# 2-RJ45.net
KiCad netlist of a schematic drawn in Altium Designer
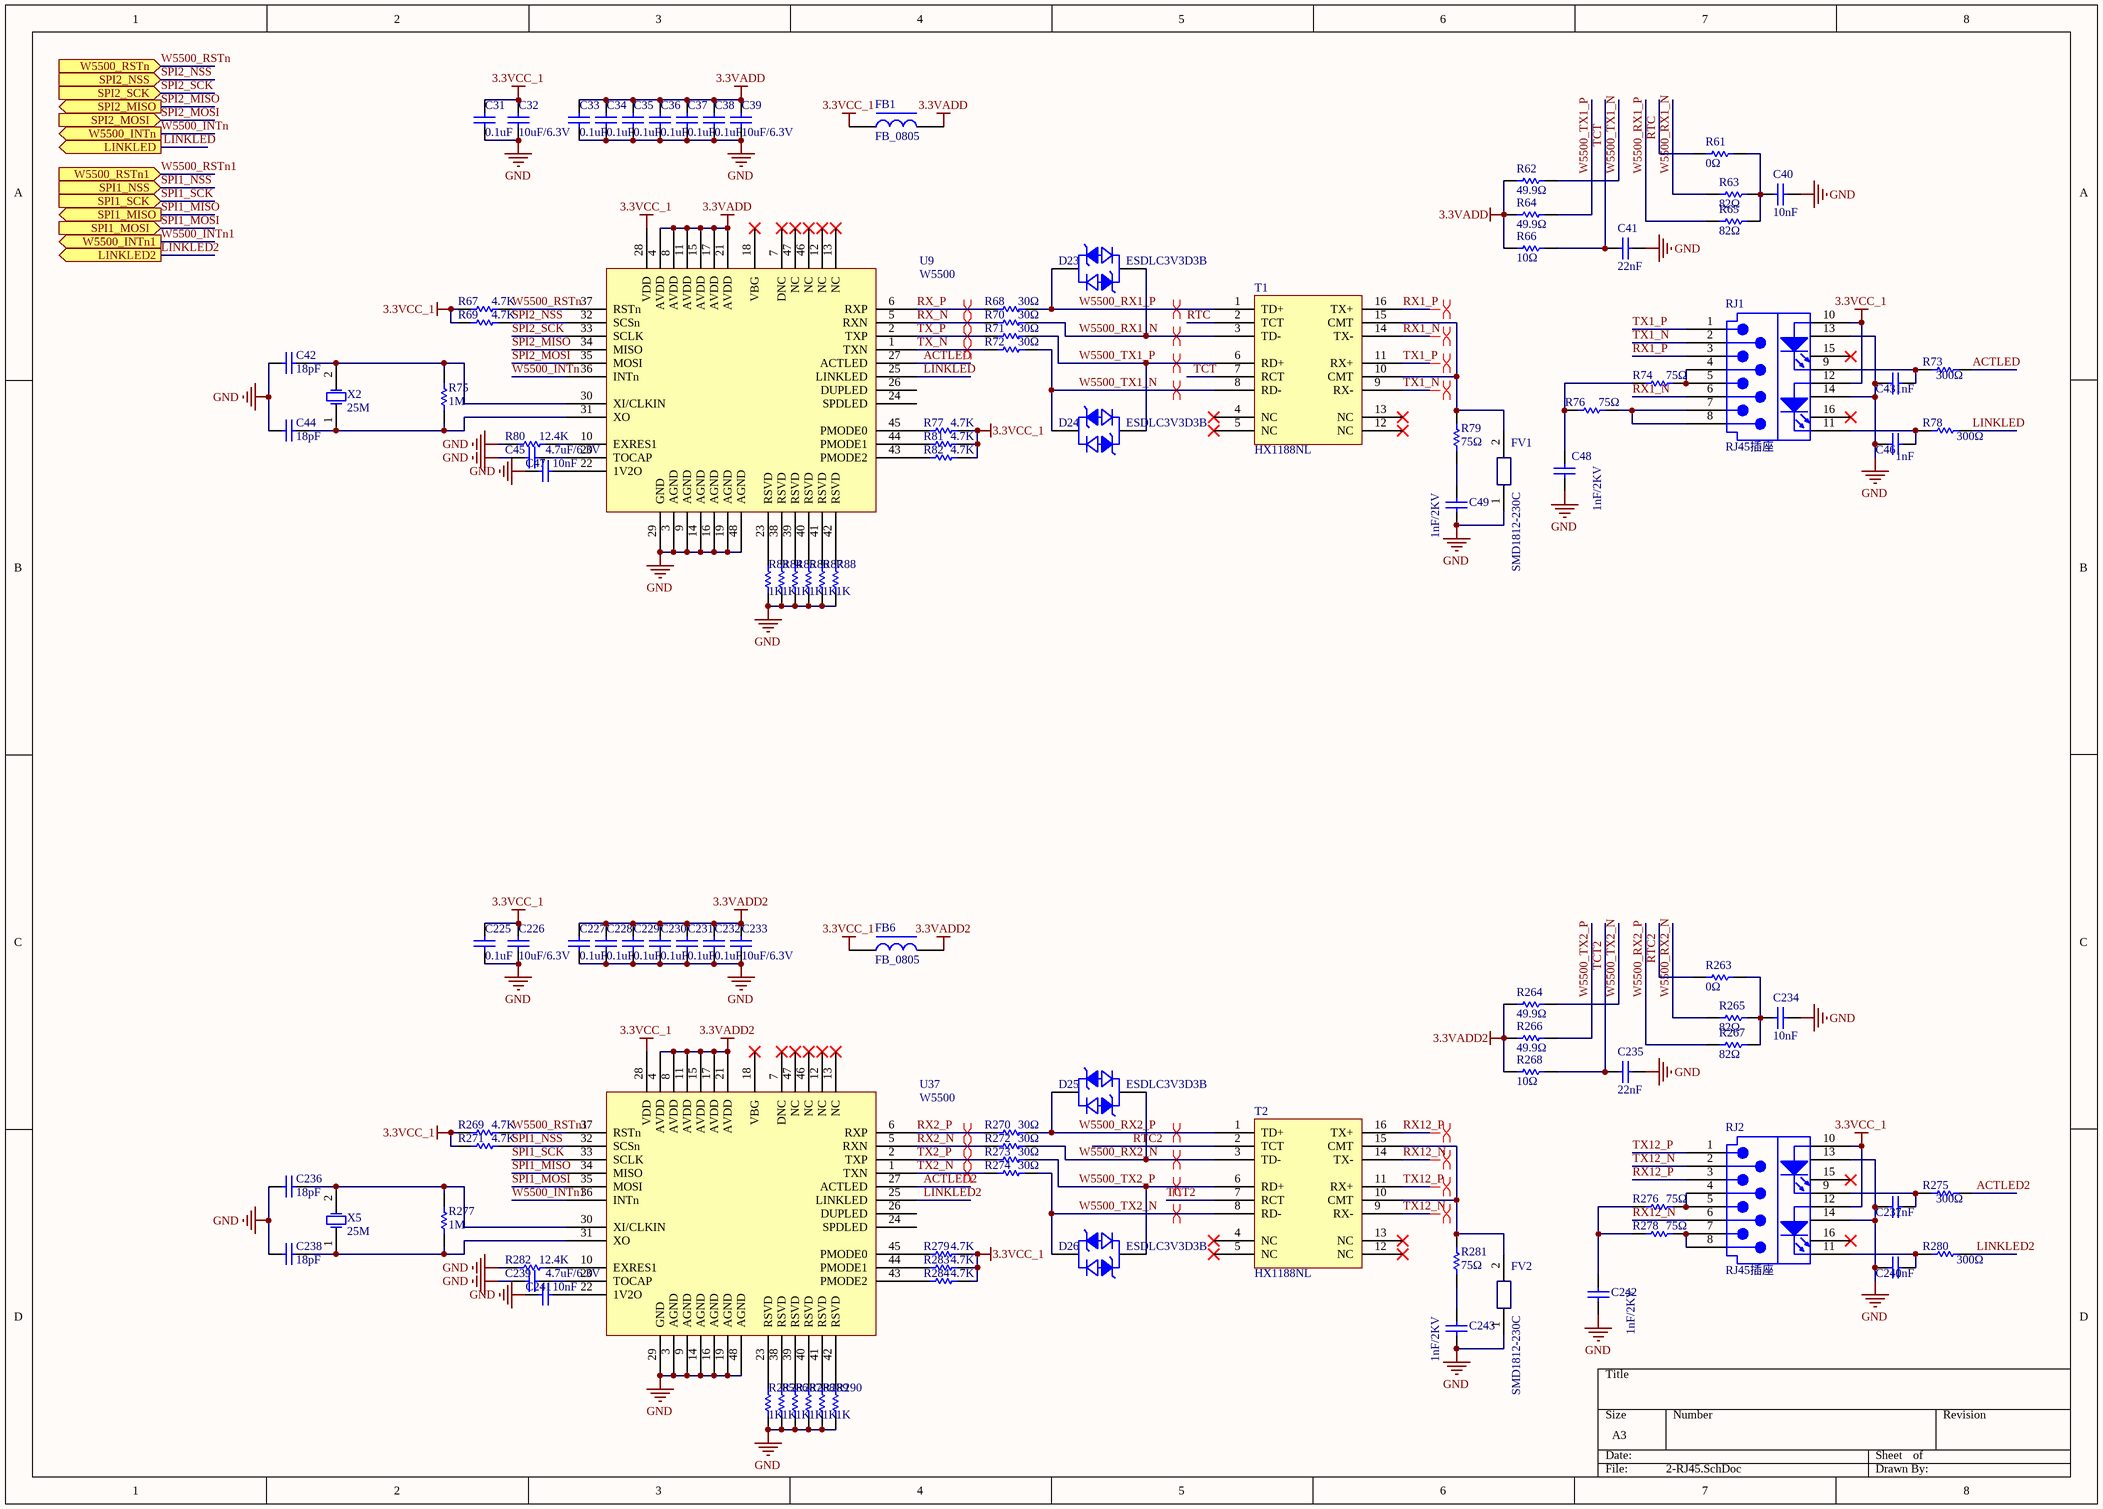
[diagram p0: 2-RJ45.SchDoc]

(export (version "E")
  (design (tool "Eeschema 10.0.6"))
  (components
    (comp (ref "C31")
      (value "0.1uF")
      (footprint "C0603")
      (description "贴片电容_GRM188R71H104KA01D_0.1uF±10%,50V,0603")
      (libsource (lib "20贴片电容0603") (part "0.1uF贴片电容"))
    )
    (comp (ref "C32")
      (value "10uF/6.3V")
      (footprint "C0603")
      (description "贴片电容_GRM188R60J106ME47D_10uF±20%,6.3V,0603")
      (libsource (lib "20贴片电容0603") (part "10uF贴片电容"))
    )
    (comp (ref "C33")
      (value "0.1uF")
      (footprint "C0603")
      (description "贴片电容_GRM188R71H104KA01D_0.1uF±10%,50V,0603")
      (libsource (lib "20贴片电容0603") (part "0.1uF贴片电容"))
    )
    (comp (ref "C34")
      (value "0.1uF")
      (footprint "C0603")
      (description "贴片电容_GRM188R71H104KA01D_0.1uF±10%,50V,0603")
      (libsource (lib "20贴片电容0603") (part "0.1uF贴片电容"))
    )
    (comp (ref "C35")
      (value "0.1uF")
      (footprint "C0603")
      (description "贴片电容_GRM188R71H104KA01D_0.1uF±10%,50V,0603")
      (libsource (lib "20贴片电容0603") (part "0.1uF贴片电容"))
    )
    (comp (ref "C36")
      (value "0.1uF")
      (footprint "C0603")
      (description "贴片电容_GRM188R71H104KA01D_0.1uF±10%,50V,0603")
      (libsource (lib "20贴片电容0603") (part "0.1uF贴片电容"))
    )
    (comp (ref "C37")
      (value "0.1uF")
      (footprint "C0603")
      (description "贴片电容_GRM188R71H104KA01D_0.1uF±10%,50V,0603")
      (libsource (lib "20贴片电容0603") (part "0.1uF贴片电容"))
    )
    (comp (ref "C38")
      (value "0.1uF")
      (footprint "C0603")
      (description "贴片电容_GRM188R71H104KA01D_0.1uF±10%,50V,0603")
      (libsource (lib "20贴片电容0603") (part "0.1uF贴片电容"))
    )
    (comp (ref "C39")
      (value "10uF/6.3V")
      (footprint "C0603")
      (description "贴片电容_GRM188R60J106ME47D_10uF±20%,6.3V,0603")
      (libsource (lib "20贴片电容0603") (part "10uF贴片电容"))
    )
    (comp (ref "C40")
      (value "10nF")
      (footprint "C0603")
      (description "C0603C103K5RAC_10nF±10%,50V,0603")
      (fields (field (name "MPN") "KEMET"))
      (libsource (lib "20贴片电容0603") (part "0.1uF贴片电容"))
    )
    (comp (ref "C41")
      (value "22nF")
      (footprint "C0603")
      (description "贴片电容_22nF±5%,50V,0603")
      (libsource (lib "20贴片电容0603") (part "27nF贴片电容"))
    )
    (comp (ref "C42")
      (value "18pF")
      (footprint "C0603")
      (description "贴片电容_GRM1885C1H180JA01D_18pF±5%,50V,0603")
      (libsource (lib "20贴片电容0603") (part "18pF贴片电容"))
    )
    (comp (ref "C43")
      (value "1nF")
      (footprint "C0603")
      (description "贴片电容_GRM188R71H102KA01_1000pF±10%,50V,0603")
      (libsource (lib "20贴片电容0603") (part "1000pF贴片电容"))
    )
    (comp (ref "C44")
      (value "18pF")
      (footprint "C0603")
      (description "贴片电容_GRM1885C1H180JA01D_18pF±5%,50V,0603")
      (libsource (lib "20贴片电容0603") (part "18pF贴片电容"))
    )
    (comp (ref "C45")
      (value "4.7uF/6.3V")
      (footprint "C0603")
      (description "GRM188R61C475K_4.7uF±10%,16V,0603")
      (fields (field (name "MPN") "Murata"))
      (libsource (lib "20贴片电容0603") (part "1uF贴片电容"))
    )
    (comp (ref "C46")
      (value "1nF")
      (footprint "C0603")
      (description "贴片电容_GRM188R71H102KA01_1000pF±10%,50V,0603")
      (libsource (lib "20贴片电容0603") (part "1000pF贴片电容"))
    )
    (comp (ref "C47")
      (value "10nF")
      (footprint "C0603")
      (description "C0603C103K5RAC_10nF±10%,50V,0603")
      (fields (field (name "MPN") "KEMET"))
      (libsource (lib "20贴片电容0603") (part "0.1uF贴片电容"))
    )
    (comp (ref "C48")
      (value "1nF/2KV")
      (footprint "C1206")
      (description "贴片电容_1206B102K202NT_1206,1000PF/2KV")
      (fields (field (name "MPN") "风华"))
      (libsource (lib "22贴片电容1210") (part "10uF贴片电容"))
    )
    (comp (ref "C49")
      (value "1nF/2KV")
      (footprint "C1206")
      (description "贴片电容_1206B102K202NT_1206,1000PF/2KV")
      (fields (field (name "MPN") "风华"))
      (libsource (lib "22贴片电容1210") (part "10uF贴片电容"))
    )
    (comp (ref "C225")
      (value "0.1uF")
      (footprint "C0603")
      (description "贴片电容_GRM188R71H104KA01D_0.1uF±10%,50V,0603")
      (libsource (lib "20贴片电容0603") (part "0.1uF贴片电容"))
    )
    (comp (ref "C226")
      (value "10uF/6.3V")
      (footprint "C0603")
      (description "贴片电容_GRM188R60J106ME47D_10uF±20%,6.3V,0603")
      (libsource (lib "20贴片电容0603") (part "10uF贴片电容"))
    )
    (comp (ref "C227")
      (value "0.1uF")
      (footprint "C0603")
      (description "贴片电容_GRM188R71H104KA01D_0.1uF±10%,50V,0603")
      (libsource (lib "20贴片电容0603") (part "0.1uF贴片电容"))
    )
    (comp (ref "C228")
      (value "0.1uF")
      (footprint "C0603")
      (description "贴片电容_GRM188R71H104KA01D_0.1uF±10%,50V,0603")
      (libsource (lib "20贴片电容0603") (part "0.1uF贴片电容"))
    )
    (comp (ref "C229")
      (value "0.1uF")
      (footprint "C0603")
      (description "贴片电容_GRM188R71H104KA01D_0.1uF±10%,50V,0603")
      (libsource (lib "20贴片电容0603") (part "0.1uF贴片电容"))
    )
    (comp (ref "C230")
      (value "0.1uF")
      (footprint "C0603")
      (description "贴片电容_GRM188R71H104KA01D_0.1uF±10%,50V,0603")
      (libsource (lib "20贴片电容0603") (part "0.1uF贴片电容"))
    )
    (comp (ref "C231")
      (value "0.1uF")
      (footprint "C0603")
      (description "贴片电容_GRM188R71H104KA01D_0.1uF±10%,50V,0603")
      (libsource (lib "20贴片电容0603") (part "0.1uF贴片电容"))
    )
    (comp (ref "C232")
      (value "0.1uF")
      (footprint "C0603")
      (description "贴片电容_GRM188R71H104KA01D_0.1uF±10%,50V,0603")
      (libsource (lib "20贴片电容0603") (part "0.1uF贴片电容"))
    )
    (comp (ref "C233")
      (value "10uF/6.3V")
      (footprint "C0603")
      (description "贴片电容_GRM188R60J106ME47D_10uF±20%,6.3V,0603")
      (libsource (lib "20贴片电容0603") (part "10uF贴片电容"))
    )
    (comp (ref "C234")
      (value "10nF")
      (footprint "C0603")
      (description "C0603C103K5RAC_10nF±10%,50V,0603")
      (fields (field (name "MPN") "KEMET"))
      (libsource (lib "20贴片电容0603") (part "0.1uF贴片电容"))
    )
    (comp (ref "C235")
      (value "22nF")
      (footprint "C0603")
      (description "贴片电容_22nF±5%,50V,0603")
      (libsource (lib "20贴片电容0603") (part "27nF贴片电容"))
    )
    (comp (ref "C236")
      (value "18pF")
      (footprint "C0603")
      (description "贴片电容_GRM1885C1H180JA01D_18pF±5%,50V,0603")
      (libsource (lib "20贴片电容0603") (part "18pF贴片电容"))
    )
    (comp (ref "C237")
      (value "1nF")
      (footprint "C0603")
      (description "贴片电容_GRM188R71H102KA01_1000pF±10%,50V,0603")
      (libsource (lib "20贴片电容0603") (part "1000pF贴片电容"))
    )
    (comp (ref "C238")
      (value "18pF")
      (footprint "C0603")
      (description "贴片电容_GRM1885C1H180JA01D_18pF±5%,50V,0603")
      (libsource (lib "20贴片电容0603") (part "18pF贴片电容"))
    )
    (comp (ref "C239")
      (value "4.7uF/6.3V")
      (footprint "C0603")
      (description "GRM188R61C475K_4.7uF±10%,16V,0603")
      (fields (field (name "MPN") "Murata"))
      (libsource (lib "20贴片电容0603") (part "1uF贴片电容"))
    )
    (comp (ref "C240")
      (value "1nF")
      (footprint "C0603")
      (description "贴片电容_GRM188R71H102KA01_1000pF±10%,50V,0603")
      (libsource (lib "20贴片电容0603") (part "1000pF贴片电容"))
    )
    (comp (ref "C241")
      (value "10nF")
      (footprint "C0603")
      (description "C0603C103K5RAC_10nF±10%,50V,0603")
      (fields (field (name "MPN") "KEMET"))
      (libsource (lib "20贴片电容0603") (part "0.1uF贴片电容"))
    )
    (comp (ref "C242")
      (value "1nF/2KV")
      (footprint "C1206")
      (description "贴片电容_1000pF/2KV")
      (libsource (lib "22贴片电容1210") (part "10uF贴片电容"))
    )
    (comp (ref "C243")
      (value "1nF/2KV")
      (footprint "C1206")
      (description "贴片电容_1000pF/2KV")
      (libsource (lib "22贴片电容1210") (part "10uF贴片电容"))
    )
    (comp (ref "D23")
      (value "ESDLC3V3D3B")
      (footprint "SOD-323")
      (description "ESD_ESDLC3V3D3B _SOD-323封装")
      (libsource (lib "40二极管") (part "ESDLC3V3D3B"))
    )
    (comp (ref "D24")
      (value "ESDLC3V3D3B")
      (footprint "SOD-323")
      (description "ESD_ESDLC3V3D3B _SOD-323封装")
      (libsource (lib "40二极管") (part "ESDLC3V3D3B"))
    )
    (comp (ref "D25")
      (value "ESDLC3V3D3B")
      (footprint "SOD-323")
      (description "ESD_ESDLC3V3D3B _SOD-323封装")
      (libsource (lib "40二极管") (part "ESDLC3V3D3B"))
    )
    (comp (ref "D26")
      (value "ESDLC3V3D3B")
      (footprint "SOD-323")
      (description "ESD_ESDLC3V3D3B _SOD-323封装")
      (libsource (lib "40二极管") (part "ESDLC3V3D3B"))
    )
    (comp (ref "FB1")
      (value "FB_0805")
      (footprint "L0805")
      (description "贴片磁珠_600R,0805")
      (libsource (lib "32贴片磁珠0805") (part "0805贴片磁珠"))
    )
    (comp (ref "FB6")
      (value "FB_0805")
      (footprint "L0805")
      (description "贴片磁珠_600R,0805")
      (libsource (lib "32贴片磁珠0805") (part "0805贴片磁珠"))
    )
    (comp (ref "FV1")
      (value "SMD1812-230C")
      (footprint "D1812")
      (description "贴片陶瓷气体放电管_SMD1812-230C_1812,230V,2KA")
      (fields (field (name "MPN") "Littelfuse"))
      (libsource (lib "104气体放电管") (part "4532-401-LF"))
    )
    (comp (ref "FV2")
      (value "SMD1812-230C")
      (footprint "D1812")
      (description "贴片陶瓷气体放电管_SMD1812-230C_1812,230V,2KA")
      (fields (field (name "MPN") "Littelfuse"))
      (libsource (lib "104气体放电管") (part "4532-401-LF"))
    )
    (comp (ref "R61")
      (value "0Ω")
      (footprint "R0603")
      (description "贴片电阻_0Ω±5%,0603")
      (libsource (lib "10贴片电阻0603") (part "0Ω贴片电阻"))
    )
    (comp (ref "R62")
      (value "49.9Ω")
      (footprint "R0603")
      (description "贴片电阻_49.9Ω±1%,0603")
      (libsource (lib "10贴片电阻0603") (part "51Ω贴片电阻"))
    )
    (comp (ref "R63")
      (value "82Ω")
      (footprint "R0603")
      (description "贴片电阻_82Ω±1%,0603")
      (libsource (lib "10贴片电阻0603") (part "51Ω贴片电阻"))
    )
    (comp (ref "R64")
      (value "49.9Ω")
      (footprint "R0603")
      (description "贴片电阻_49.9Ω±1%,0603")
      (libsource (lib "10贴片电阻0603") (part "51Ω贴片电阻"))
    )
    (comp (ref "R65")
      (value "82Ω")
      (footprint "R0603")
      (description "贴片电阻_82Ω±1%,0603")
      (libsource (lib "10贴片电阻0603") (part "51Ω贴片电阻"))
    )
    (comp (ref "R66")
      (value "10Ω")
      (footprint "R0603")
      (description "贴片电阻_10Ω±5%,0603")
      (libsource (lib "10贴片电阻0603") (part "10Ω贴片电阻"))
    )
    (comp (ref "R67")
      (value "4.7K")
      (footprint "R0603")
      (description "贴片电阻_4.7K±5%,0603")
      (libsource (lib "10贴片电阻0603") (part "4.7K贴片电阻"))
    )
    (comp (ref "R68")
      (value "30Ω")
      (footprint "R0603")
      (description "贴片电阻_30Ω±5%,0603")
      (libsource (lib "10贴片电阻0603") (part "30Ω贴片电阻"))
    )
    (comp (ref "R69")
      (value "4.7K")
      (footprint "R0603")
      (description "贴片电阻_4.7K±5%,0603")
      (libsource (lib "10贴片电阻0603") (part "4.7K贴片电阻"))
    )
    (comp (ref "R70")
      (value "30Ω")
      (footprint "R0603")
      (description "贴片电阻_30Ω±5%,0603")
      (libsource (lib "10贴片电阻0603") (part "30Ω贴片电阻"))
    )
    (comp (ref "R71")
      (value "30Ω")
      (footprint "R0603")
      (description "贴片电阻_30Ω±5%,0603")
      (libsource (lib "10贴片电阻0603") (part "30Ω贴片电阻"))
    )
    (comp (ref "R72")
      (value "30Ω")
      (footprint "R0603")
      (description "贴片电阻_30Ω±5%,0603")
      (libsource (lib "10贴片电阻0603") (part "30Ω贴片电阻"))
    )
    (comp (ref "R73")
      (value "300Ω")
      (footprint "R0603")
      (description "贴片电阻_300Ω±5%,0603")
      (libsource (lib "10贴片电阻0603") (part "300Ω贴片电阻"))
    )
    (comp (ref "R74")
      (value "75Ω")
      (footprint "R0805")
      (description "贴片电阻_75Ω±5%,0805")
      (libsource (lib "11贴片电阻0805") (part "75Ω贴片电阻"))
    )
    (comp (ref "R75")
      (value "1M")
      (footprint "R0603")
      (description "贴片电阻_1M±5%,0603")
      (libsource (lib "10贴片电阻0603") (part "1M贴片电阻"))
    )
    (comp (ref "R76")
      (value "75Ω")
      (footprint "R0805")
      (description "贴片电阻_75Ω±5%,0805")
      (libsource (lib "11贴片电阻0805") (part "75Ω贴片电阻"))
    )
    (comp (ref "R77")
      (value "4.7K")
      (footprint "R0603")
      (description "贴片电阻_4.7K±5%,0603")
      (libsource (lib "10贴片电阻0603") (part "4.7K贴片电阻"))
    )
    (comp (ref "R78")
      (value "300Ω")
      (footprint "R0603")
      (description "贴片电阻_300Ω±5%,0603")
      (libsource (lib "10贴片电阻0603") (part "300Ω贴片电阻"))
    )
    (comp (ref "R79")
      (value "75Ω")
      (footprint "R1206")
      (description "贴片电阻_75Ω±5%,1206")
      (libsource (lib "11贴片电阻0805") (part "75Ω贴片电阻"))
    )
    (comp (ref "R80")
      (value "12.4K")
      (footprint "R0603")
      (description "贴片电阻_12.4K±1%,0603")
      (libsource (lib "10贴片电阻0603") (part "12K贴片电阻"))
    )
    (comp (ref "R81")
      (value "4.7K")
      (footprint "R0603")
      (description "贴片电阻_4.7K±5%,0603")
      (libsource (lib "10贴片电阻0603") (part "4.7K贴片电阻"))
    )
    (comp (ref "R82")
      (value "4.7K")
      (footprint "R0603")
      (description "贴片电阻_4.7K±5%,0603")
      (libsource (lib "10贴片电阻0603") (part "4.7K贴片电阻"))
    )
    (comp (ref "R83")
      (value "1K")
      (footprint "R0603")
      (description "贴片电阻_1K±5%,0603")
      (libsource (lib "10贴片电阻0603") (part "1K贴片电阻"))
    )
    (comp (ref "R84")
      (value "1K")
      (footprint "R0603")
      (description "贴片电阻_1K±5%,0603")
      (libsource (lib "10贴片电阻0603") (part "1K贴片电阻"))
    )
    (comp (ref "R85")
      (value "1K")
      (footprint "R0603")
      (description "贴片电阻_1K±5%,0603")
      (libsource (lib "10贴片电阻0603") (part "1K贴片电阻"))
    )
    (comp (ref "R86")
      (value "1K")
      (footprint "R0603")
      (description "贴片电阻_1K±5%,0603")
      (libsource (lib "10贴片电阻0603") (part "1K贴片电阻"))
    )
    (comp (ref "R87")
      (value "1K")
      (footprint "R0603")
      (description "贴片电阻_1K±5%,0603")
      (libsource (lib "10贴片电阻0603") (part "1K贴片电阻"))
    )
    (comp (ref "R88")
      (value "1K")
      (footprint "R0603")
      (description "贴片电阻_1K±5%,0603")
      (libsource (lib "10贴片电阻0603") (part "1K贴片电阻"))
    )
    (comp (ref "R263")
      (value "0Ω")
      (footprint "R0603")
      (description "贴片电阻_0Ω±5%,0603")
      (libsource (lib "10贴片电阻0603") (part "0Ω贴片电阻"))
    )
    (comp (ref "R264")
      (value "49.9Ω")
      (footprint "R0603")
      (description "贴片电阻_49.9Ω±1%,0603")
      (libsource (lib "10贴片电阻0603") (part "51Ω贴片电阻"))
    )
    (comp (ref "R265")
      (value "82Ω")
      (footprint "R0603")
      (description "贴片电阻_82Ω±1%,0603")
      (libsource (lib "10贴片电阻0603") (part "51Ω贴片电阻"))
    )
    (comp (ref "R266")
      (value "49.9Ω")
      (footprint "R0603")
      (description "贴片电阻_49.9Ω±1%,0603")
      (libsource (lib "10贴片电阻0603") (part "51Ω贴片电阻"))
    )
    (comp (ref "R267")
      (value "82Ω")
      (footprint "R0603")
      (description "贴片电阻_82Ω±1%,0603")
      (libsource (lib "10贴片电阻0603") (part "51Ω贴片电阻"))
    )
    (comp (ref "R268")
      (value "10Ω")
      (footprint "R0603")
      (description "贴片电阻_10Ω±5%,0603")
      (libsource (lib "10贴片电阻0603") (part "10Ω贴片电阻"))
    )
    (comp (ref "R269")
      (value "4.7K")
      (footprint "R0603")
      (description "贴片电阻_4.7K±5%,0603")
      (libsource (lib "10贴片电阻0603") (part "4.7K贴片电阻"))
    )
    (comp (ref "R270")
      (value "30Ω")
      (footprint "R0603")
      (description "贴片电阻_30Ω±5%,0603")
      (libsource (lib "10贴片电阻0603") (part "30Ω贴片电阻"))
    )
    (comp (ref "R271")
      (value "4.7K")
      (footprint "R0603")
      (description "贴片电阻_4.7K±5%,0603")
      (libsource (lib "10贴片电阻0603") (part "4.7K贴片电阻"))
    )
    (comp (ref "R272")
      (value "30Ω")
      (footprint "R0603")
      (description "贴片电阻_30Ω±5%,0603")
      (libsource (lib "10贴片电阻0603") (part "30Ω贴片电阻"))
    )
    (comp (ref "R273")
      (value "30Ω")
      (footprint "R0603")
      (description "贴片电阻_30Ω±5%,0603")
      (libsource (lib "10贴片电阻0603") (part "30Ω贴片电阻"))
    )
    (comp (ref "R274")
      (value "30Ω")
      (footprint "R0603")
      (description "贴片电阻_30Ω±5%,0603")
      (libsource (lib "10贴片电阻0603") (part "30Ω贴片电阻"))
    )
    (comp (ref "R275")
      (value "300Ω")
      (footprint "R0603")
      (description "贴片电阻_300Ω±5%,0603")
      (libsource (lib "10贴片电阻0603") (part "300Ω贴片电阻"))
    )
    (comp (ref "R276")
      (value "75Ω")
      (footprint "R0805")
      (description "贴片电阻_75Ω±5%,0805")
      (libsource (lib "11贴片电阻0805") (part "75Ω贴片电阻"))
    )
    (comp (ref "R277")
      (value "1M")
      (footprint "R0603")
      (description "贴片电阻_1M±5%,0603")
      (libsource (lib "10贴片电阻0603") (part "1M贴片电阻"))
    )
    (comp (ref "R278")
      (value "75Ω")
      (footprint "R0805")
      (description "贴片电阻_75Ω±5%,0805")
      (libsource (lib "11贴片电阻0805") (part "75Ω贴片电阻"))
    )
    (comp (ref "R279")
      (value "4.7K")
      (footprint "R0603")
      (description "贴片电阻_4.7K±5%,0603")
      (libsource (lib "10贴片电阻0603") (part "4.7K贴片电阻"))
    )
    (comp (ref "R280")
      (value "300Ω")
      (footprint "R0603")
      (description "贴片电阻_300Ω±5%,0603")
      (libsource (lib "10贴片电阻0603") (part "300Ω贴片电阻"))
    )
    (comp (ref "R281")
      (value "75Ω")
      (footprint "R1206")
      (description "贴片电阻_75Ω±5%,1206")
      (libsource (lib "11贴片电阻0805") (part "75Ω贴片电阻"))
    )
    (comp (ref "R282")
      (value "12.4K")
      (footprint "R0603")
      (description "贴片电阻_12.4K±1%,0603")
      (libsource (lib "10贴片电阻0603") (part "12K贴片电阻"))
    )
    (comp (ref "R283")
      (value "4.7K")
      (footprint "R0603")
      (description "贴片电阻_4.7K±5%,0603")
      (libsource (lib "10贴片电阻0603") (part "4.7K贴片电阻"))
    )
    (comp (ref "R284")
      (value "4.7K")
      (footprint "R0603")
      (description "贴片电阻_4.7K±5%,0603")
      (libsource (lib "10贴片电阻0603") (part "4.7K贴片电阻"))
    )
    (comp (ref "R285")
      (value "1K")
      (footprint "R0603")
      (description "贴片电阻_1K±5%,0603")
      (libsource (lib "10贴片电阻0603") (part "1K贴片电阻"))
    )
    (comp (ref "R286")
      (value "1K")
      (footprint "R0603")
      (description "贴片电阻_1K±5%,0603")
      (libsource (lib "10贴片电阻0603") (part "1K贴片电阻"))
    )
    (comp (ref "R287")
      (value "1K")
      (footprint "R0603")
      (description "贴片电阻_1K±5%,0603")
      (libsource (lib "10贴片电阻0603") (part "1K贴片电阻"))
    )
    (comp (ref "R288")
      (value "1K")
      (footprint "R0603")
      (description "贴片电阻_1K±5%,0603")
      (libsource (lib "10贴片电阻0603") (part "1K贴片电阻"))
    )
    (comp (ref "R289")
      (value "1K")
      (footprint "R0603")
      (description "贴片电阻_1K±5%,0603")
      (libsource (lib "10贴片电阻0603") (part "1K贴片电阻"))
    )
    (comp (ref "R290")
      (value "1K")
      (footprint "R0603")
      (description "贴片电阻_1K±5%,0603")
      (libsource (lib "10贴片电阻0603") (part "1K贴片电阻"))
    )
    (comp (ref "RJ1")
      (value "RJ45插座")
      (footprint "RJ45TH-1x1-2R54-LED")
      (description "RJ45插座_1*1,带左黄右绿灯,弯脚")
      (fields (field (name "MPN") "朱迅"))
      (libsource (lib "91连接器") (part "RJ45弯脚带灯"))
    )
    (comp (ref "RJ2")
      (value "RJ45插座")
      (footprint "RJ45TH-1x1-2R54-LED")
      (description "RJ45插座_1*1,带左黄右绿灯,弯脚")
      (fields (field (name "MPN") "朱迅"))
      (libsource (lib "91连接器") (part "RJ45弯脚带灯"))
    )
    (comp (ref "T1")
      (value "HX1188NL")
      (footprint "SOP16-1R27-7R11x12R7")
      (description "网络变压器_HX1188NL_百兆,SOIC16")
      (libsource (lib "89网络变压器") (part "HX1188NL"))
    )
    (comp (ref "T2")
      (value "HX1188NL")
      (footprint "SOP16-1R27-7R11x12R7")
      (description "网络变压器_HX1188NL_百兆,SOIC16")
      (libsource (lib "89网络变压器") (part "HX1188NL"))
    )
    (comp (ref "U9")
      (value "W5500")
      (footprint "TQFN48-0R5-7X7")
      (description "以太网控制器_W5500_LQFP48")
      (libsource (lib "86网口芯片") (part "W5500"))
    )
    (comp (ref "U37")
      (value "W5500")
      (footprint "TQFN48-0R5-7X7")
      (description "以太网控制器_W5500_LQFP48")
      (libsource (lib "86网口芯片") (part "W5500"))
    )
    (comp (ref "X2")
      (value "25M")
      (footprint "CRY2SM-6R0x3R5")
      (description "贴片无源晶体_25MHz,30ppm,6035封装")
      (libsource (lib "60振荡器") (part "25M贴片无源晶体"))
    )
    (comp (ref "X5")
      (value "25M")
      (footprint "CRY2SM-6R0x3R5")
      (description "贴片无源晶体_25MHz,封装6035")
      (libsource (lib "60振荡器") (part "8M贴片无源晶体"))
    )
  )
  (nets
    (net (code "1") (name "/ACTLED") (class "Default")
      (node (ref "R73") (pin "2") (pinfunction "2_2") (pintype "passive"))
      (node (ref "U9") (pin "27") (pinfunction "ACTLED_27") (pintype "passive"))
    )
    (net (code "2") (name "/ACTLED2") (class "Default")
      (node (ref "R275") (pin "2") (pinfunction "2_2") (pintype "passive"))
      (node (ref "U37") (pin "27") (pinfunction "ACTLED_27") (pintype "passive"))
    )
    (net (code "3") (name "/LINKLED") (class "Default")
      (node (ref "R78") (pin "2") (pinfunction "2_2") (pintype "passive"))
      (node (ref "U9") (pin "25") (pinfunction "LINKLED_25") (pintype "passive"))
    )
    (net (code "4") (name "/LINKLED2") (class "Default")
      (node (ref "R280") (pin "2") (pinfunction "2_2") (pintype "passive"))
      (node (ref "U37") (pin "25") (pinfunction "LINKLED_25") (pintype "passive"))
    )
    (net (code "5") (name "/RTC") (class "Default")
      (node (ref "R61") (pin "2") (pinfunction "2_2") (pintype "passive"))
      (node (ref "T1") (pin "2") (pinfunction "TCT_2") (pintype "passive"))
    )
    (net (code "6") (name "/RTC2") (class "Default")
      (node (ref "R263") (pin "2") (pinfunction "2_2") (pintype "passive"))
      (node (ref "T2") (pin "2") (pinfunction "TCT_2") (pintype "passive"))
    )
    (net (code "7") (name "/RX1_N") (class "Default")
      (node (ref "RJ1") (pin "6") (pinfunction "RX-_6") (pintype "passive"))
      (node (ref "T1") (pin "14") (pinfunction "TX-_14") (pintype "passive"))
    )
    (net (code "8") (name "/RX1_P") (class "Default")
      (node (ref "RJ1") (pin "3") (pinfunction "RX+_3") (pintype "passive"))
      (node (ref "T1") (pin "16") (pinfunction "TX+_16") (pintype "passive"))
    )
    (net (code "9") (name "/RX2_N") (class "Default")
      (node (ref "R272") (pin "1") (pinfunction "1_1") (pintype "passive"))
      (node (ref "U37") (pin "5") (pinfunction "RXN_5") (pintype "passive"))
    )
    (net (code "10") (name "/RX2_P") (class "Default")
      (node (ref "R270") (pin "1") (pinfunction "1_1") (pintype "passive"))
      (node (ref "U37") (pin "6") (pinfunction "RXP_6") (pintype "passive"))
    )
    (net (code "11") (name "/RX12_N") (class "Default")
      (node (ref "RJ2") (pin "6") (pinfunction "RX-_6") (pintype "passive"))
      (node (ref "T2") (pin "14") (pinfunction "TX-_14") (pintype "passive"))
    )
    (net (code "12") (name "/RX12_P") (class "Default")
      (node (ref "RJ2") (pin "3") (pinfunction "RX+_3") (pintype "passive"))
      (node (ref "T2") (pin "16") (pinfunction "TX+_16") (pintype "passive"))
    )
    (net (code "13") (name "/RX_N") (class "Default")
      (node (ref "R70") (pin "1") (pinfunction "1_1") (pintype "passive"))
      (node (ref "U9") (pin "5") (pinfunction "RXN_5") (pintype "passive"))
    )
    (net (code "14") (name "/RX_P") (class "Default")
      (node (ref "R68") (pin "1") (pinfunction "1_1") (pintype "passive"))
      (node (ref "U9") (pin "6") (pinfunction "RXP_6") (pintype "passive"))
    )
    (net (code "15") (name "/SPI1_MISO") (class "Default")
      (node (ref "U37") (pin "34") (pinfunction "MISO_34") (pintype "passive"))
    )
    (net (code "16") (name "/SPI1_MOSI") (class "Default")
      (node (ref "U37") (pin "35") (pinfunction "MOSI_35") (pintype "passive"))
    )
    (net (code "17") (name "/SPI1_NSS") (class "Default")
      (node (ref "R271") (pin "1") (pinfunction "1_1") (pintype "passive"))
      (node (ref "U37") (pin "32") (pinfunction "SCSn_32") (pintype "passive"))
    )
    (net (code "18") (name "/SPI1_SCK") (class "Default")
      (node (ref "U37") (pin "33") (pinfunction "SCLK_33") (pintype "passive"))
    )
    (net (code "19") (name "/SPI2_MISO") (class "Default")
      (node (ref "U9") (pin "34") (pinfunction "MISO_34") (pintype "passive"))
    )
    (net (code "20") (name "/SPI2_MOSI") (class "Default")
      (node (ref "U9") (pin "35") (pinfunction "MOSI_35") (pintype "passive"))
    )
    (net (code "21") (name "/SPI2_NSS") (class "Default")
      (node (ref "R69") (pin "1") (pinfunction "1_1") (pintype "passive"))
      (node (ref "U9") (pin "32") (pinfunction "SCSn_32") (pintype "passive"))
    )
    (net (code "22") (name "/SPI2_SCK") (class "Default")
      (node (ref "U9") (pin "33") (pinfunction "SCLK_33") (pintype "passive"))
    )
    (net (code "23") (name "/TCT") (class "Default")
      (node (ref "C41") (pin "2") (pinfunction "2_2") (pintype "passive"))
      (node (ref "R66") (pin "1") (pinfunction "1_1") (pintype "passive"))
      (node (ref "T1") (pin "7") (pinfunction "RCT_7") (pintype "passive"))
    )
    (net (code "24") (name "/TCT2") (class "Default")
      (node (ref "C235") (pin "2") (pinfunction "2_2") (pintype "passive"))
      (node (ref "R268") (pin "1") (pinfunction "1_1") (pintype "passive"))
      (node (ref "T2") (pin "7") (pinfunction "RCT_7") (pintype "passive"))
    )
    (net (code "25") (name "/TX1_N") (class "Default")
      (node (ref "RJ1") (pin "2") (pinfunction "TX-_2") (pintype "passive"))
      (node (ref "T1") (pin "9") (pinfunction "RX-_9") (pintype "passive"))
    )
    (net (code "26") (name "/TX1_P") (class "Default")
      (node (ref "RJ1") (pin "1") (pinfunction "TX+_1") (pintype "passive"))
      (node (ref "T1") (pin "11") (pinfunction "RX+_11") (pintype "passive"))
    )
    (net (code "27") (name "/TX2_N") (class "Default")
      (node (ref "R274") (pin "1") (pinfunction "1_1") (pintype "passive"))
      (node (ref "U37") (pin "1") (pinfunction "TXN_1") (pintype "passive"))
    )
    (net (code "28") (name "/TX2_P") (class "Default")
      (node (ref "R273") (pin "1") (pinfunction "1_1") (pintype "passive"))
      (node (ref "U37") (pin "2") (pinfunction "TXP_2") (pintype "passive"))
    )
    (net (code "29") (name "/TX12_N") (class "Default")
      (node (ref "RJ2") (pin "2") (pinfunction "TX-_2") (pintype "passive"))
      (node (ref "T2") (pin "9") (pinfunction "RX-_9") (pintype "passive"))
    )
    (net (code "30") (name "/TX12_P") (class "Default")
      (node (ref "RJ2") (pin "1") (pinfunction "TX+_1") (pintype "passive"))
      (node (ref "T2") (pin "11") (pinfunction "RX+_11") (pintype "passive"))
    )
    (net (code "31") (name "/TX_N") (class "Default")
      (node (ref "R72") (pin "1") (pinfunction "1_1") (pintype "passive"))
      (node (ref "U9") (pin "1") (pinfunction "TXN_1") (pintype "passive"))
    )
    (net (code "32") (name "/TX_P") (class "Default")
      (node (ref "R71") (pin "1") (pinfunction "1_1") (pintype "passive"))
      (node (ref "U9") (pin "2") (pinfunction "TXP_2") (pintype "passive"))
    )
    (net (code "33") (name "/W5500_INTn") (class "Default")
      (node (ref "U9") (pin "36") (pinfunction "INTn_36") (pintype "passive"))
    )
    (net (code "34") (name "/W5500_INTn1") (class "Default")
      (node (ref "U37") (pin "36") (pinfunction "INTn_36") (pintype "passive"))
    )
    (net (code "35") (name "/W5500_RSTn") (class "Default")
      (node (ref "R67") (pin "1") (pinfunction "1_1") (pintype "passive"))
      (node (ref "U9") (pin "37") (pinfunction "RSTn_37") (pintype "passive"))
    )
    (net (code "36") (name "/W5500_RSTn1") (class "Default")
      (node (ref "R269") (pin "1") (pinfunction "1_1") (pintype "passive"))
      (node (ref "U37") (pin "37") (pinfunction "RSTn_37") (pintype "passive"))
    )
    (net (code "37") (name "/W5500_RX1_N") (class "Default")
      (node (ref "D23") (pin "2") (pinfunction "2_2") (pintype "passive"))
      (node (ref "R63") (pin "2") (pinfunction "2_2") (pintype "passive"))
      (node (ref "R70") (pin "2") (pinfunction "2_2") (pintype "passive"))
      (node (ref "T1") (pin "3") (pinfunction "TD-_3") (pintype "passive"))
    )
    (net (code "38") (name "/W5500_RX1_P") (class "Default")
      (node (ref "D23") (pin "1") (pinfunction "1_1") (pintype "passive"))
      (node (ref "R65") (pin "2") (pinfunction "2_2") (pintype "passive"))
      (node (ref "R68") (pin "2") (pinfunction "2_2") (pintype "passive"))
      (node (ref "T1") (pin "1") (pinfunction "TD+_1") (pintype "passive"))
    )
    (net (code "39") (name "/W5500_RX2_N") (class "Default")
      (node (ref "D25") (pin "2") (pinfunction "2_2") (pintype "passive"))
      (node (ref "R265") (pin "2") (pinfunction "2_2") (pintype "passive"))
      (node (ref "R272") (pin "2") (pinfunction "2_2") (pintype "passive"))
      (node (ref "T2") (pin "3") (pinfunction "TD-_3") (pintype "passive"))
    )
    (net (code "40") (name "/W5500_RX2_P") (class "Default")
      (node (ref "D25") (pin "1") (pinfunction "1_1") (pintype "passive"))
      (node (ref "R267") (pin "2") (pinfunction "2_2") (pintype "passive"))
      (node (ref "R270") (pin "2") (pinfunction "2_2") (pintype "passive"))
      (node (ref "T2") (pin "1") (pinfunction "TD+_1") (pintype "passive"))
    )
    (net (code "41") (name "/W5500_TX1_N") (class "Default")
      (node (ref "D24") (pin "1") (pinfunction "1_1") (pintype "passive"))
      (node (ref "R62") (pin "1") (pinfunction "1_1") (pintype "passive"))
      (node (ref "R72") (pin "2") (pinfunction "2_2") (pintype "passive"))
      (node (ref "T1") (pin "8") (pinfunction "RD-_8") (pintype "passive"))
    )
    (net (code "42") (name "/W5500_TX1_P") (class "Default")
      (node (ref "D24") (pin "2") (pinfunction "2_2") (pintype "passive"))
      (node (ref "R64") (pin "1") (pinfunction "1_1") (pintype "passive"))
      (node (ref "R71") (pin "2") (pinfunction "2_2") (pintype "passive"))
      (node (ref "T1") (pin "6") (pinfunction "RD+_6") (pintype "passive"))
    )
    (net (code "43") (name "/W5500_TX2_N") (class "Default")
      (node (ref "D26") (pin "1") (pinfunction "1_1") (pintype "passive"))
      (node (ref "R264") (pin "1") (pinfunction "1_1") (pintype "passive"))
      (node (ref "R274") (pin "2") (pinfunction "2_2") (pintype "passive"))
      (node (ref "T2") (pin "8") (pinfunction "RD-_8") (pintype "passive"))
    )
    (net (code "44") (name "/W5500_TX2_P") (class "Default")
      (node (ref "D26") (pin "2") (pinfunction "2_2") (pintype "passive"))
      (node (ref "R266") (pin "1") (pinfunction "1_1") (pintype "passive"))
      (node (ref "R273") (pin "2") (pinfunction "2_2") (pintype "passive"))
      (node (ref "T2") (pin "6") (pinfunction "RD+_6") (pintype "passive"))
    )
    (net (code "45") (name "3.3VADD") (class "Default")
      (node (ref "C33") (pin "2") (pinfunction "2_2") (pintype "passive"))
      (node (ref "C34") (pin "2") (pinfunction "2_2") (pintype "passive"))
      (node (ref "C35") (pin "2") (pinfunction "2_2") (pintype "passive"))
      (node (ref "C36") (pin "2") (pinfunction "2_2") (pintype "passive"))
      (node (ref "C37") (pin "2") (pinfunction "2_2") (pintype "passive"))
      (node (ref "C38") (pin "2") (pinfunction "2_2") (pintype "passive"))
      (node (ref "C39") (pin "2") (pinfunction "2_2") (pintype "passive"))
      (node (ref "FB1") (pin "2") (pinfunction "2_2") (pintype "passive"))
      (node (ref "R62") (pin "2") (pinfunction "2_2") (pintype "passive"))
      (node (ref "R64") (pin "2") (pinfunction "2_2") (pintype "passive"))
      (node (ref "R66") (pin "2") (pinfunction "2_2") (pintype "passive"))
      (node (ref "U9") (pin "11") (pinfunction "AVDD_11") (pintype "passive"))
      (node (ref "U9") (pin "15") (pinfunction "AVDD_15") (pintype "passive"))
      (node (ref "U9") (pin "17") (pinfunction "AVDD_17") (pintype "passive"))
      (node (ref "U9") (pin "21") (pinfunction "AVDD_21") (pintype "passive"))
      (node (ref "U9") (pin "4") (pinfunction "AVDD_4") (pintype "passive"))
      (node (ref "U9") (pin "8") (pinfunction "AVDD_8") (pintype "passive"))
    )
    (net (code "46") (name "3.3VADD2") (class "Default")
      (node (ref "C227") (pin "2") (pinfunction "2_2") (pintype "passive"))
      (node (ref "C228") (pin "2") (pinfunction "2_2") (pintype "passive"))
      (node (ref "C229") (pin "2") (pinfunction "2_2") (pintype "passive"))
      (node (ref "C230") (pin "2") (pinfunction "2_2") (pintype "passive"))
      (node (ref "C231") (pin "2") (pinfunction "2_2") (pintype "passive"))
      (node (ref "C232") (pin "2") (pinfunction "2_2") (pintype "passive"))
      (node (ref "C233") (pin "2") (pinfunction "2_2") (pintype "passive"))
      (node (ref "FB6") (pin "2") (pinfunction "2_2") (pintype "passive"))
      (node (ref "R264") (pin "2") (pinfunction "2_2") (pintype "passive"))
      (node (ref "R266") (pin "2") (pinfunction "2_2") (pintype "passive"))
      (node (ref "R268") (pin "2") (pinfunction "2_2") (pintype "passive"))
      (node (ref "U37") (pin "11") (pinfunction "AVDD_11") (pintype "passive"))
      (node (ref "U37") (pin "15") (pinfunction "AVDD_15") (pintype "passive"))
      (node (ref "U37") (pin "17") (pinfunction "AVDD_17") (pintype "passive"))
      (node (ref "U37") (pin "21") (pinfunction "AVDD_21") (pintype "passive"))
      (node (ref "U37") (pin "4") (pinfunction "AVDD_4") (pintype "passive"))
      (node (ref "U37") (pin "8") (pinfunction "AVDD_8") (pintype "passive"))
    )
    (net (code "47") (name "3.3VCC_1") (class "Default")
      (node (ref "C225") (pin "2") (pinfunction "2_2") (pintype "passive"))
      (node (ref "C226") (pin "2") (pinfunction "2_2") (pintype "passive"))
      (node (ref "C31") (pin "2") (pinfunction "2_2") (pintype "passive"))
      (node (ref "C32") (pin "2") (pinfunction "2_2") (pintype "passive"))
      (node (ref "FB1") (pin "1") (pinfunction "1_1") (pintype "passive"))
      (node (ref "FB6") (pin "1") (pinfunction "1_1") (pintype "passive"))
      (node (ref "R269") (pin "2") (pinfunction "2_2") (pintype "passive"))
      (node (ref "R271") (pin "2") (pinfunction "2_2") (pintype "passive"))
      (node (ref "R279") (pin "2") (pinfunction "2_2") (pintype "passive"))
      (node (ref "R283") (pin "2") (pinfunction "2_2") (pintype "passive"))
      (node (ref "R284") (pin "2") (pinfunction "2_2") (pintype "passive"))
      (node (ref "R67") (pin "2") (pinfunction "2_2") (pintype "passive"))
      (node (ref "R69") (pin "2") (pinfunction "2_2") (pintype "passive"))
      (node (ref "R77") (pin "2") (pinfunction "2_2") (pintype "passive"))
      (node (ref "R81") (pin "2") (pinfunction "2_2") (pintype "passive"))
      (node (ref "R82") (pin "2") (pinfunction "2_2") (pintype "passive"))
      (node (ref "RJ1") (pin "10") (pinfunction "A1_10") (pintype "passive"))
      (node (ref "RJ1") (pin "12") (pinfunction "A2_12") (pintype "passive"))
      (node (ref "RJ2") (pin "10") (pinfunction "A1_10") (pintype "passive"))
      (node (ref "RJ2") (pin "12") (pinfunction "A2_12") (pintype "passive"))
      (node (ref "U37") (pin "28") (pinfunction "VDD_28") (pintype "passive"))
      (node (ref "U9") (pin "28") (pinfunction "VDD_28") (pintype "passive"))
    )
    (net (code "48") (name "GND") (class "Default")
      (node (ref "C225") (pin "1") (pinfunction "1_1") (pintype "passive"))
      (node (ref "C226") (pin "1") (pinfunction "1_1") (pintype "passive"))
      (node (ref "C227") (pin "1") (pinfunction "1_1") (pintype "passive"))
      (node (ref "C228") (pin "1") (pinfunction "1_1") (pintype "passive"))
      (node (ref "C229") (pin "1") (pinfunction "1_1") (pintype "passive"))
      (node (ref "C230") (pin "1") (pinfunction "1_1") (pintype "passive"))
      (node (ref "C231") (pin "1") (pinfunction "1_1") (pintype "passive"))
      (node (ref "C232") (pin "1") (pinfunction "1_1") (pintype "passive"))
      (node (ref "C233") (pin "1") (pinfunction "1_1") (pintype "passive"))
      (node (ref "C234") (pin "1") (pinfunction "1_1") (pintype "passive"))
      (node (ref "C235") (pin "1") (pinfunction "1_1") (pintype "passive"))
      (node (ref "C236") (pin "1") (pinfunction "1_1") (pintype "passive"))
      (node (ref "C237") (pin "1") (pinfunction "1_1") (pintype "passive"))
      (node (ref "C238") (pin "1") (pinfunction "1_1") (pintype "passive"))
      (node (ref "C239") (pin "1") (pinfunction "1_1") (pintype "passive"))
      (node (ref "C240") (pin "1") (pinfunction "1_1") (pintype "passive"))
      (node (ref "C241") (pin "2") (pinfunction "2_2") (pintype "passive"))
      (node (ref "C242") (pin "1") (pinfunction "1_1") (pintype "passive"))
      (node (ref "C243") (pin "1") (pinfunction "1_1") (pintype "passive"))
      (node (ref "C31") (pin "1") (pinfunction "1_1") (pintype "passive"))
      (node (ref "C32") (pin "1") (pinfunction "1_1") (pintype "passive"))
      (node (ref "C33") (pin "1") (pinfunction "1_1") (pintype "passive"))
      (node (ref "C34") (pin "1") (pinfunction "1_1") (pintype "passive"))
      (node (ref "C35") (pin "1") (pinfunction "1_1") (pintype "passive"))
      (node (ref "C36") (pin "1") (pinfunction "1_1") (pintype "passive"))
      (node (ref "C37") (pin "1") (pinfunction "1_1") (pintype "passive"))
      (node (ref "C38") (pin "1") (pinfunction "1_1") (pintype "passive"))
      (node (ref "C39") (pin "1") (pinfunction "1_1") (pintype "passive"))
      (node (ref "C40") (pin "1") (pinfunction "1_1") (pintype "passive"))
      (node (ref "C41") (pin "1") (pinfunction "1_1") (pintype "passive"))
      (node (ref "C42") (pin "1") (pinfunction "1_1") (pintype "passive"))
      (node (ref "C43") (pin "1") (pinfunction "1_1") (pintype "passive"))
      (node (ref "C44") (pin "1") (pinfunction "1_1") (pintype "passive"))
      (node (ref "C45") (pin "1") (pinfunction "1_1") (pintype "passive"))
      (node (ref "C46") (pin "1") (pinfunction "1_1") (pintype "passive"))
      (node (ref "C47") (pin "2") (pinfunction "2_2") (pintype "passive"))
      (node (ref "C48") (pin "1") (pinfunction "1_1") (pintype "passive"))
      (node (ref "C49") (pin "1") (pinfunction "1_1") (pintype "passive"))
      (node (ref "FV1") (pin "1") (pinfunction "1_1") (pintype "passive"))
      (node (ref "FV2") (pin "1") (pinfunction "1_1") (pintype "passive"))
      (node (ref "R282") (pin "1") (pinfunction "1_1") (pintype "passive"))
      (node (ref "R285") (pin "1") (pinfunction "1_1") (pintype "passive"))
      (node (ref "R286") (pin "1") (pinfunction "1_1") (pintype "passive"))
      (node (ref "R287") (pin "1") (pinfunction "1_1") (pintype "passive"))
      (node (ref "R288") (pin "1") (pinfunction "1_1") (pintype "passive"))
      (node (ref "R289") (pin "1") (pinfunction "1_1") (pintype "passive"))
      (node (ref "R290") (pin "1") (pinfunction "1_1") (pintype "passive"))
      (node (ref "R80") (pin "1") (pinfunction "1_1") (pintype "passive"))
      (node (ref "R83") (pin "1") (pinfunction "1_1") (pintype "passive"))
      (node (ref "R84") (pin "1") (pinfunction "1_1") (pintype "passive"))
      (node (ref "R85") (pin "1") (pinfunction "1_1") (pintype "passive"))
      (node (ref "R86") (pin "1") (pinfunction "1_1") (pintype "passive"))
      (node (ref "R87") (pin "1") (pinfunction "1_1") (pintype "passive"))
      (node (ref "R88") (pin "1") (pinfunction "1_1") (pintype "passive"))
      (node (ref "RJ1") (pin "13") (pinfunction "13_13") (pintype "passive"))
      (node (ref "RJ1") (pin "14") (pinfunction "14_14") (pintype "passive"))
      (node (ref "RJ2") (pin "13") (pinfunction "13_13") (pintype "passive"))
      (node (ref "RJ2") (pin "14") (pinfunction "14_14") (pintype "passive"))
      (node (ref "U37") (pin "14") (pinfunction "AGND_14") (pintype "passive"))
      (node (ref "U37") (pin "16") (pinfunction "AGND_16") (pintype "passive"))
      (node (ref "U37") (pin "19") (pinfunction "AGND_19") (pintype "passive"))
      (node (ref "U37") (pin "29") (pinfunction "GND_29") (pintype "passive"))
      (node (ref "U37") (pin "3") (pinfunction "AGND_3") (pintype "passive"))
      (node (ref "U37") (pin "48") (pinfunction "AGND_48") (pintype "passive"))
      (node (ref "U37") (pin "9") (pinfunction "AGND_9") (pintype "passive"))
      (node (ref "U9") (pin "14") (pinfunction "AGND_14") (pintype "passive"))
      (node (ref "U9") (pin "16") (pinfunction "AGND_16") (pintype "passive"))
      (node (ref "U9") (pin "19") (pinfunction "AGND_19") (pintype "passive"))
      (node (ref "U9") (pin "29") (pinfunction "GND_29") (pintype "passive"))
      (node (ref "U9") (pin "3") (pinfunction "AGND_3") (pintype "passive"))
      (node (ref "U9") (pin "48") (pinfunction "AGND_48") (pintype "passive"))
      (node (ref "U9") (pin "9") (pinfunction "AGND_9") (pintype "passive"))
    )
    (net (code "49") (name "Net-(C40-Pad2)") (class "Default")
      (node (ref "C40") (pin "2") (pinfunction "2_2") (pintype "passive"))
      (node (ref "R61") (pin "1") (pinfunction "1_1") (pintype "passive"))
      (node (ref "R63") (pin "1") (pinfunction "1_1") (pintype "passive"))
      (node (ref "R65") (pin "1") (pinfunction "1_1") (pintype "passive"))
    )
    (net (code "50") (name "Net-(C48-Pad2)") (class "Default")
      (node (ref "C48") (pin "2") (pinfunction "2_2") (pintype "passive"))
      (node (ref "R74") (pin "1") (pinfunction "1_1") (pintype "passive"))
      (node (ref "R76") (pin "1") (pinfunction "1_1") (pintype "passive"))
    )
    (net (code "51") (name "Net-(C49-Pad2)") (class "Default")
      (node (ref "C49") (pin "2") (pinfunction "2_2") (pintype "passive"))
      (node (ref "R79") (pin "1") (pinfunction "1_1") (pintype "passive"))
    )
    (net (code "52") (name "Net-(C234-Pad2)") (class "Default")
      (node (ref "C234") (pin "2") (pinfunction "2_2") (pintype "passive"))
      (node (ref "R263") (pin "1") (pinfunction "1_1") (pintype "passive"))
      (node (ref "R265") (pin "1") (pinfunction "1_1") (pintype "passive"))
      (node (ref "R267") (pin "1") (pinfunction "1_1") (pintype "passive"))
    )
    (net (code "53") (name "Net-(C242-Pad2)") (class "Default")
      (node (ref "C242") (pin "2") (pinfunction "2_2") (pintype "passive"))
      (node (ref "R276") (pin "1") (pinfunction "1_1") (pintype "passive"))
      (node (ref "R278") (pin "1") (pinfunction "1_1") (pintype "passive"))
    )
    (net (code "54") (name "Net-(C243-Pad2)") (class "Default")
      (node (ref "C243") (pin "2") (pinfunction "2_2") (pintype "passive"))
      (node (ref "R281") (pin "1") (pinfunction "1_1") (pintype "passive"))
    )
    (net (code "55") (name "Net-(FV1-Pad2)") (class "Default")
      (node (ref "FV1") (pin "2") (pinfunction "2_2") (pintype "passive"))
      (node (ref "R79") (pin "2") (pinfunction "2_2") (pintype "passive"))
      (node (ref "T1") (pin "10") (pinfunction "CMT_10") (pintype "passive"))
      (node (ref "T1") (pin "15") (pinfunction "CMT_15") (pintype "passive"))
    )
    (net (code "56") (name "Net-(FV2-Pad2)") (class "Default")
      (node (ref "FV2") (pin "2") (pinfunction "2_2") (pintype "passive"))
      (node (ref "R281") (pin "2") (pinfunction "2_2") (pintype "passive"))
      (node (ref "T2") (pin "10") (pinfunction "CMT_10") (pintype "passive"))
      (node (ref "T2") (pin "15") (pinfunction "CMT_15") (pintype "passive"))
    )
    (net (code "57") (name "Net-(R74-Pad2)") (class "Default")
      (node (ref "R74") (pin "2") (pinfunction "2_2") (pintype "passive"))
      (node (ref "RJ1") (pin "4") (pinfunction "NC_4") (pintype "passive"))
      (node (ref "RJ1") (pin "5") (pinfunction "NC_5") (pintype "passive"))
    )
    (net (code "58") (name "Net-(R76-Pad2)") (class "Default")
      (node (ref "R76") (pin "2") (pinfunction "2_2") (pintype "passive"))
      (node (ref "RJ1") (pin "7") (pinfunction "NC_7") (pintype "passive"))
      (node (ref "RJ1") (pin "8") (pinfunction "NC_8") (pintype "passive"))
    )
    (net (code "59") (name "Net-(R83-Pad2)") (class "Default")
      (node (ref "R83") (pin "2") (pinfunction "2_2") (pintype "passive"))
      (node (ref "U9") (pin "23") (pinfunction "RSVD_23") (pintype "passive"))
    )
    (net (code "60") (name "Net-(R84-Pad2)") (class "Default")
      (node (ref "R84") (pin "2") (pinfunction "2_2") (pintype "passive"))
      (node (ref "U9") (pin "38") (pinfunction "RSVD_38") (pintype "passive"))
    )
    (net (code "61") (name "Net-(R85-Pad2)") (class "Default")
      (node (ref "R85") (pin "2") (pinfunction "2_2") (pintype "passive"))
      (node (ref "U9") (pin "39") (pinfunction "RSVD_39") (pintype "passive"))
    )
    (net (code "62") (name "Net-(R86-Pad2)") (class "Default")
      (node (ref "R86") (pin "2") (pinfunction "2_2") (pintype "passive"))
      (node (ref "U9") (pin "40") (pinfunction "RSVD_40") (pintype "passive"))
    )
    (net (code "63") (name "Net-(R87-Pad2)") (class "Default")
      (node (ref "R87") (pin "2") (pinfunction "2_2") (pintype "passive"))
      (node (ref "U9") (pin "41") (pinfunction "RSVD_41") (pintype "passive"))
    )
    (net (code "64") (name "Net-(R88-Pad2)") (class "Default")
      (node (ref "R88") (pin "2") (pinfunction "2_2") (pintype "passive"))
      (node (ref "U9") (pin "42") (pinfunction "RSVD_42") (pintype "passive"))
    )
    (net (code "65") (name "Net-(R276-Pad2)") (class "Default")
      (node (ref "R276") (pin "2") (pinfunction "2_2") (pintype "passive"))
      (node (ref "RJ2") (pin "4") (pinfunction "NC_4") (pintype "passive"))
      (node (ref "RJ2") (pin "5") (pinfunction "NC_5") (pintype "passive"))
    )
    (net (code "66") (name "Net-(R278-Pad2)") (class "Default")
      (node (ref "R278") (pin "2") (pinfunction "2_2") (pintype "passive"))
      (node (ref "RJ2") (pin "7") (pinfunction "NC_7") (pintype "passive"))
      (node (ref "RJ2") (pin "8") (pinfunction "NC_8") (pintype "passive"))
    )
    (net (code "67") (name "Net-(R285-Pad2)") (class "Default")
      (node (ref "R285") (pin "2") (pinfunction "2_2") (pintype "passive"))
      (node (ref "U37") (pin "23") (pinfunction "RSVD_23") (pintype "passive"))
    )
    (net (code "68") (name "Net-(R286-Pad2)") (class "Default")
      (node (ref "R286") (pin "2") (pinfunction "2_2") (pintype "passive"))
      (node (ref "U37") (pin "38") (pinfunction "RSVD_38") (pintype "passive"))
    )
    (net (code "69") (name "Net-(R287-Pad2)") (class "Default")
      (node (ref "R287") (pin "2") (pinfunction "2_2") (pintype "passive"))
      (node (ref "U37") (pin "39") (pinfunction "RSVD_39") (pintype "passive"))
    )
    (net (code "70") (name "Net-(R288-Pad2)") (class "Default")
      (node (ref "R288") (pin "2") (pinfunction "2_2") (pintype "passive"))
      (node (ref "U37") (pin "40") (pinfunction "RSVD_40") (pintype "passive"))
    )
    (net (code "71") (name "Net-(R289-Pad2)") (class "Default")
      (node (ref "R289") (pin "2") (pinfunction "2_2") (pintype "passive"))
      (node (ref "U37") (pin "41") (pinfunction "RSVD_41") (pintype "passive"))
    )
    (net (code "72") (name "Net-(R290-Pad2)") (class "Default")
      (node (ref "R290") (pin "2") (pinfunction "2_2") (pintype "passive"))
      (node (ref "U37") (pin "42") (pinfunction "RSVD_42") (pintype "passive"))
    )
    (net (code "73") (name "Net-(RJ1-K1)") (class "Default")
      (node (ref "C43") (pin "2") (pinfunction "2_2") (pintype "passive"))
      (node (ref "R73") (pin "1") (pinfunction "1_1") (pintype "passive"))
      (node (ref "RJ1") (pin "9") (pinfunction "K1_9") (pintype "passive"))
    )
    (net (code "74") (name "Net-(RJ1-K2)") (class "Default")
      (node (ref "C46") (pin "2") (pinfunction "2_2") (pintype "passive"))
      (node (ref "R78") (pin "1") (pinfunction "1_1") (pintype "passive"))
      (node (ref "RJ1") (pin "11") (pinfunction "K2_11") (pintype "passive"))
    )
    (net (code "75") (name "Net-(RJ2-K1)") (class "Default")
      (node (ref "C237") (pin "2") (pinfunction "2_2") (pintype "passive"))
      (node (ref "R275") (pin "1") (pinfunction "1_1") (pintype "passive"))
      (node (ref "RJ2") (pin "9") (pinfunction "K1_9") (pintype "passive"))
    )
    (net (code "76") (name "Net-(RJ2-K2)") (class "Default")
      (node (ref "C240") (pin "2") (pinfunction "2_2") (pintype "passive"))
      (node (ref "R280") (pin "1") (pinfunction "1_1") (pintype "passive"))
      (node (ref "RJ2") (pin "11") (pinfunction "K2_11") (pintype "passive"))
    )
    (net (code "77") (name "Net-(U9-1V2O)") (class "Default")
      (node (ref "C47") (pin "1") (pinfunction "1_1") (pintype "passive"))
      (node (ref "U9") (pin "22") (pinfunction "1V2O_22") (pintype "passive"))
    )
    (net (code "78") (name "Net-(U9-EXRES1)") (class "Default")
      (node (ref "R80") (pin "2") (pinfunction "2_2") (pintype "passive"))
      (node (ref "U9") (pin "10") (pinfunction "EXRES1_10") (pintype "passive"))
    )
    (net (code "79") (name "Net-(U9-PMODE0)") (class "Default")
      (node (ref "R77") (pin "1") (pinfunction "1_1") (pintype "passive"))
      (node (ref "U9") (pin "45") (pinfunction "PMODE0_45") (pintype "passive"))
    )
    (net (code "80") (name "Net-(U9-PMODE1)") (class "Default")
      (node (ref "R81") (pin "1") (pinfunction "1_1") (pintype "passive"))
      (node (ref "U9") (pin "44") (pinfunction "PMODE1_44") (pintype "passive"))
    )
    (net (code "81") (name "Net-(U9-PMODE2)") (class "Default")
      (node (ref "R82") (pin "1") (pinfunction "1_1") (pintype "passive"))
      (node (ref "U9") (pin "43") (pinfunction "PMODE2_43") (pintype "passive"))
    )
    (net (code "82") (name "Net-(U9-TOCAP)") (class "Default")
      (node (ref "C45") (pin "2") (pinfunction "2_2") (pintype "passive"))
      (node (ref "U9") (pin "20") (pinfunction "TOCAP_20") (pintype "passive"))
    )
    (net (code "83") (name "Net-(U9-XI{slash}CLKIN)") (class "Default")
      (node (ref "C42") (pin "2") (pinfunction "2_2") (pintype "passive"))
      (node (ref "R75") (pin "2") (pinfunction "2_2") (pintype "passive"))
      (node (ref "U9") (pin "30") (pinfunction "XI/CLKIN_30") (pintype "passive"))
      (node (ref "X2") (pin "2") (pinfunction "OSC2_2") (pintype "passive"))
    )
    (net (code "84") (name "Net-(U9-XO)") (class "Default")
      (node (ref "C44") (pin "2") (pinfunction "2_2") (pintype "passive"))
      (node (ref "R75") (pin "1") (pinfunction "1_1") (pintype "passive"))
      (node (ref "U9") (pin "31") (pinfunction "XO_31") (pintype "passive"))
      (node (ref "X2") (pin "1") (pinfunction "OSC1_1") (pintype "passive"))
    )
    (net (code "85") (name "Net-(U37-1V2O)") (class "Default")
      (node (ref "C241") (pin "1") (pinfunction "1_1") (pintype "passive"))
      (node (ref "U37") (pin "22") (pinfunction "1V2O_22") (pintype "passive"))
    )
    (net (code "86") (name "Net-(U37-EXRES1)") (class "Default")
      (node (ref "R282") (pin "2") (pinfunction "2_2") (pintype "passive"))
      (node (ref "U37") (pin "10") (pinfunction "EXRES1_10") (pintype "passive"))
    )
    (net (code "87") (name "Net-(U37-PMODE0)") (class "Default")
      (node (ref "R279") (pin "1") (pinfunction "1_1") (pintype "passive"))
      (node (ref "U37") (pin "45") (pinfunction "PMODE0_45") (pintype "passive"))
    )
    (net (code "88") (name "Net-(U37-PMODE1)") (class "Default")
      (node (ref "R283") (pin "1") (pinfunction "1_1") (pintype "passive"))
      (node (ref "U37") (pin "44") (pinfunction "PMODE1_44") (pintype "passive"))
    )
    (net (code "89") (name "Net-(U37-PMODE2)") (class "Default")
      (node (ref "R284") (pin "1") (pinfunction "1_1") (pintype "passive"))
      (node (ref "U37") (pin "43") (pinfunction "PMODE2_43") (pintype "passive"))
    )
    (net (code "90") (name "Net-(U37-TOCAP)") (class "Default")
      (node (ref "C239") (pin "2") (pinfunction "2_2") (pintype "passive"))
      (node (ref "U37") (pin "20") (pinfunction "TOCAP_20") (pintype "passive"))
    )
    (net (code "91") (name "Net-(U37-XI{slash}CLKIN)") (class "Default")
      (node (ref "C236") (pin "2") (pinfunction "2_2") (pintype "passive"))
      (node (ref "R277") (pin "2") (pinfunction "2_2") (pintype "passive"))
      (node (ref "U37") (pin "30") (pinfunction "XI/CLKIN_30") (pintype "passive"))
      (node (ref "X5") (pin "2") (pinfunction "OSC2_2") (pintype "passive"))
    )
    (net (code "92") (name "Net-(U37-XO)") (class "Default")
      (node (ref "C238") (pin "2") (pinfunction "2_2") (pintype "passive"))
      (node (ref "R277") (pin "1") (pinfunction "1_1") (pintype "passive"))
      (node (ref "U37") (pin "31") (pinfunction "XO_31") (pintype "passive"))
      (node (ref "X5") (pin "1") (pinfunction "OSC1_1") (pintype "passive"))
    )
    (net (code "93") (name "unconnected-(RJ1-Pad15)") (class "Default")
      (node (ref "RJ1") (pin "15") (pinfunction "15_15") (pintype "passive+no_connect"))
    )
    (net (code "94") (name "unconnected-(RJ1-Pad16)") (class "Default")
      (node (ref "RJ1") (pin "16") (pinfunction "16_16") (pintype "passive+no_connect"))
    )
    (net (code "95") (name "unconnected-(RJ2-Pad15)") (class "Default")
      (node (ref "RJ2") (pin "15") (pinfunction "15_15") (pintype "passive+no_connect"))
    )
    (net (code "96") (name "unconnected-(RJ2-Pad16)") (class "Default")
      (node (ref "RJ2") (pin "16") (pinfunction "16_16") (pintype "passive+no_connect"))
    )
    (net (code "97") (name "unconnected-(T1-NC-Pad4)") (class "Default")
      (node (ref "T1") (pin "4") (pinfunction "NC_4") (pintype "passive+no_connect"))
    )
    (net (code "98") (name "unconnected-(T1-NC-Pad5)") (class "Default")
      (node (ref "T1") (pin "5") (pinfunction "NC_5") (pintype "passive+no_connect"))
    )
    (net (code "99") (name "unconnected-(T1-NC-Pad12)") (class "Default")
      (node (ref "T1") (pin "12") (pinfunction "NC_12") (pintype "passive+no_connect"))
    )
    (net (code "100") (name "unconnected-(T1-NC-Pad13)") (class "Default")
      (node (ref "T1") (pin "13") (pinfunction "NC_13") (pintype "passive+no_connect"))
    )
    (net (code "101") (name "unconnected-(T2-NC-Pad4)") (class "Default")
      (node (ref "T2") (pin "4") (pinfunction "NC_4") (pintype "passive+no_connect"))
    )
    (net (code "102") (name "unconnected-(T2-NC-Pad5)") (class "Default")
      (node (ref "T2") (pin "5") (pinfunction "NC_5") (pintype "passive+no_connect"))
    )
    (net (code "103") (name "unconnected-(T2-NC-Pad12)") (class "Default")
      (node (ref "T2") (pin "12") (pinfunction "NC_12") (pintype "passive+no_connect"))
    )
    (net (code "104") (name "unconnected-(T2-NC-Pad13)") (class "Default")
      (node (ref "T2") (pin "13") (pinfunction "NC_13") (pintype "passive+no_connect"))
    )
    (net (code "105") (name "unconnected-(U9-DNC-Pad7)") (class "Default")
      (node (ref "U9") (pin "7") (pinfunction "DNC_7") (pintype "passive+no_connect"))
    )
    (net (code "106") (name "unconnected-(U9-DUPLED-Pad26)") (class "Default")
      (node (ref "U9") (pin "26") (pinfunction "DUPLED_26") (pintype "passive"))
    )
    (net (code "107") (name "unconnected-(U9-NC-Pad12)") (class "Default")
      (node (ref "U9") (pin "12") (pinfunction "NC_12") (pintype "passive+no_connect"))
    )
    (net (code "108") (name "unconnected-(U9-NC-Pad13)") (class "Default")
      (node (ref "U9") (pin "13") (pinfunction "NC_13") (pintype "passive+no_connect"))
    )
    (net (code "109") (name "unconnected-(U9-NC-Pad46)") (class "Default")
      (node (ref "U9") (pin "46") (pinfunction "NC_46") (pintype "passive+no_connect"))
    )
    (net (code "110") (name "unconnected-(U9-NC-Pad47)") (class "Default")
      (node (ref "U9") (pin "47") (pinfunction "NC_47") (pintype "passive+no_connect"))
    )
    (net (code "111") (name "unconnected-(U9-SPDLED-Pad24)") (class "Default")
      (node (ref "U9") (pin "24") (pinfunction "SPDLED_24") (pintype "passive"))
    )
    (net (code "112") (name "unconnected-(U9-VBG-Pad18)") (class "Default")
      (node (ref "U9") (pin "18") (pinfunction "VBG_18") (pintype "passive+no_connect"))
    )
    (net (code "113") (name "unconnected-(U37-DNC-Pad7)") (class "Default")
      (node (ref "U37") (pin "7") (pinfunction "DNC_7") (pintype "passive+no_connect"))
    )
    (net (code "114") (name "unconnected-(U37-DUPLED-Pad26)") (class "Default")
      (node (ref "U37") (pin "26") (pinfunction "DUPLED_26") (pintype "passive"))
    )
    (net (code "115") (name "unconnected-(U37-NC-Pad12)") (class "Default")
      (node (ref "U37") (pin "12") (pinfunction "NC_12") (pintype "passive+no_connect"))
    )
    (net (code "116") (name "unconnected-(U37-NC-Pad13)") (class "Default")
      (node (ref "U37") (pin "13") (pinfunction "NC_13") (pintype "passive+no_connect"))
    )
    (net (code "117") (name "unconnected-(U37-NC-Pad46)") (class "Default")
      (node (ref "U37") (pin "46") (pinfunction "NC_46") (pintype "passive+no_connect"))
    )
    (net (code "118") (name "unconnected-(U37-NC-Pad47)") (class "Default")
      (node (ref "U37") (pin "47") (pinfunction "NC_47") (pintype "passive+no_connect"))
    )
    (net (code "119") (name "unconnected-(U37-SPDLED-Pad24)") (class "Default")
      (node (ref "U37") (pin "24") (pinfunction "SPDLED_24") (pintype "passive"))
    )
    (net (code "120") (name "unconnected-(U37-VBG-Pad18)") (class "Default")
      (node (ref "U37") (pin "18") (pinfunction "VBG_18") (pintype "passive+no_connect"))
    )
  )
)
